# Avometer_v1_1_Simple.net
KiCad netlist of a schematic drawn in Altium Designer
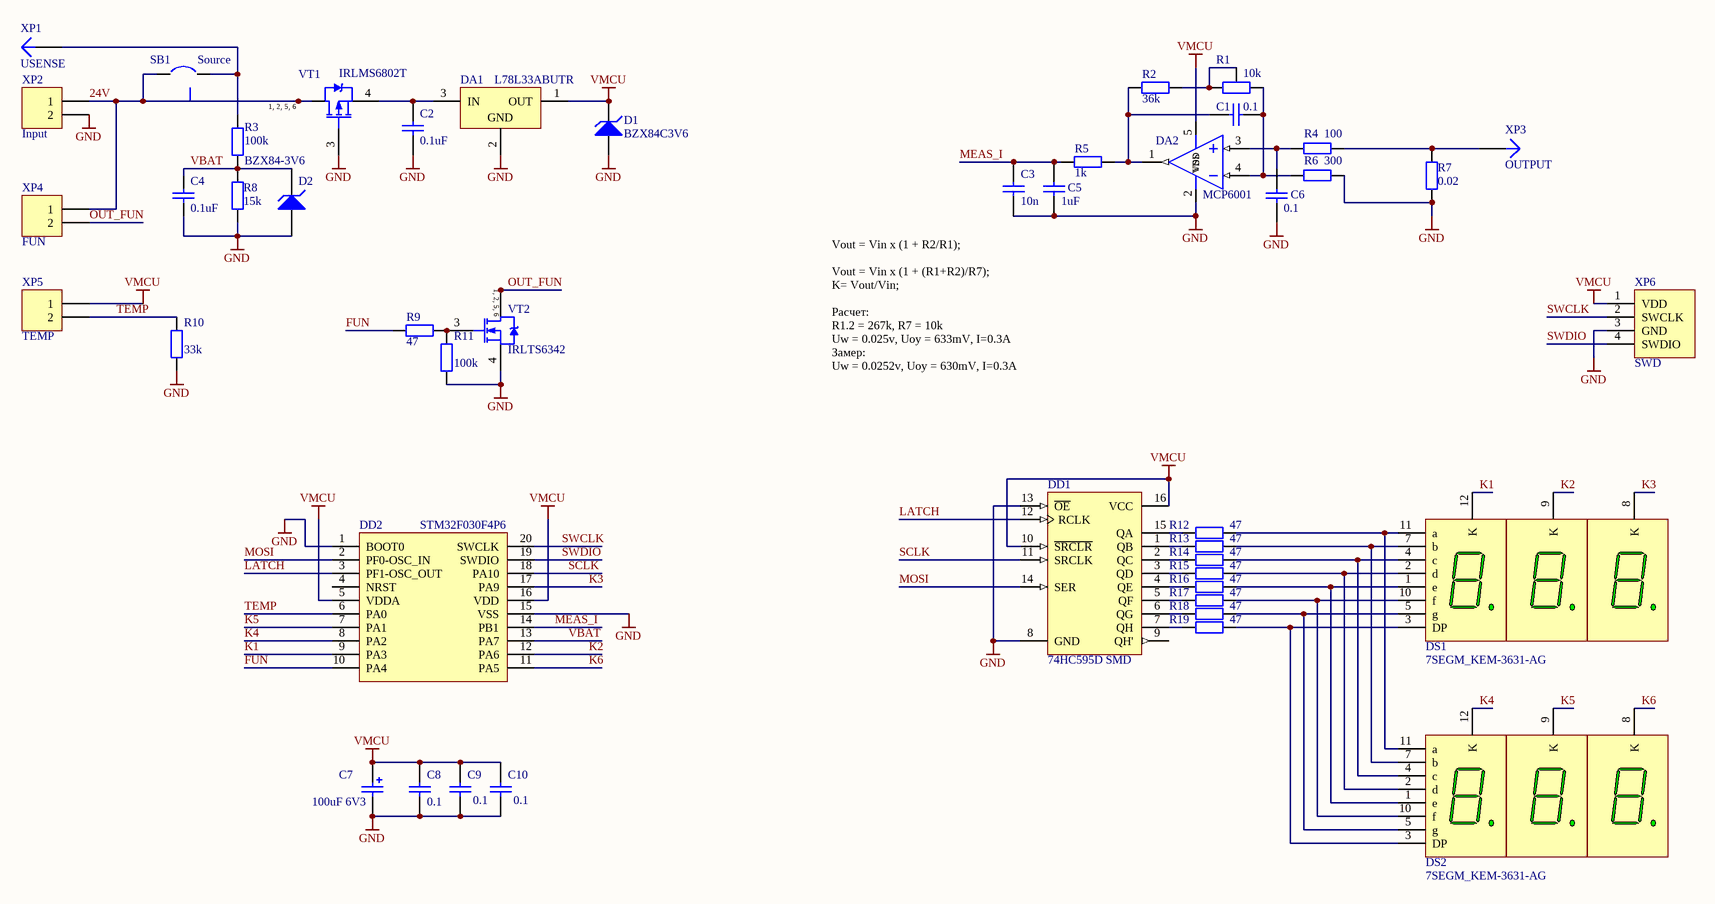
[diagram p0: Avometer v1.1 Simple.SchDoc]

(export (version "E")
  (design (tool "Eeschema 10.0.6"))
  (components
    (comp (ref "C1")
      (value "0.1")
      (footprint "CAP 0603_N")
      (description "Capacitor SMD")
      (libsource (lib "MyLibrary") (part "CAP_SMD"))
    )
    (comp (ref "C2")
      (value "0.1uF")
      (footprint "CAP 0603_N")
      (description "Capacitor SMD")
      (libsource (lib "MyLibrary") (part "CAP_SMD"))
    )
    (comp (ref "C3")
      (value "10n")
      (footprint "CAP 0603_N")
      (description "Capacitor SMD")
      (libsource (lib "MyLibrary") (part "CAP_SMD"))
    )
    (comp (ref "C4") (value "0.1uF") (footprint "CAP 0603_N") (libsource (lib "") (part "CAP_SMD_1")))
    (comp (ref "C5")
      (value "1uF")
      (footprint "CAP 0603_N")
      (description "Capacitor SMD")
      (libsource (lib "MyLibrary") (part "CAP_SMD"))
    )
    (comp (ref "C6")
      (value "0.1")
      (footprint "CAP 0603_N")
      (description "Capacitor SMD")
      (libsource (lib "MyLibrary") (part "CAP_SMD"))
    )
    (comp (ref "C7")
      (value "100uF 6V3")
      (footprint "CAP_TANT_B_TYPE_3528-21")
      (description "Capacitor SMD Tantalum")
      (libsource (lib "MyLibrary") (part "CAP_SMD_TANT"))
    )
    (comp (ref "C8")
      (value "0.1")
      (footprint "CAP 0603_N")
      (description "Capacitor SMD")
      (libsource (lib "MyLibrary") (part "CAP_SMD"))
    )
    (comp (ref "C9")
      (value "0.1")
      (footprint "CAP 0603_N")
      (description "Capacitor SMD")
      (libsource (lib "MyLibrary") (part "CAP_SMD"))
    )
    (comp (ref "C10")
      (value "0.1")
      (footprint "CAP 0603_N")
      (description "Capacitor SMD")
      (libsource (lib "MyLibrary") (part "CAP_SMD"))
    )
    (comp (ref "D1")
      (value "BZX84C3V6")
      (footprint "SOT-23_L")
      (description "Zener Diode")
      (fields (field (name "PUBLISHER") "Altium Limited"))
      (libsource (lib "") (part "BZX84_1"))
    )
    (comp (ref "D2")
      (value "BZX84-3V6")
      (footprint "SOT-23_L")
      (description "Zener Diode")
      (fields (field (name "PUBLISHER") "Altium Limited"))
      (libsource (lib "MyLibrary") (part "BZX84"))
    )
    (comp (ref "DA1")
      (value "L78L33ABUTR")
      (footprint "SOT-89")
      (description "Vin=30V Positive Voltage Regulator")
      (fields (field (name "PUBLISHER") "Altium Limited"))
      (libsource (lib "MyLibrary") (part "L78L33ABUTR"))
    )
    (comp (ref "DA2")
      (value "MCP6001")
      (footprint "SOT-23-5_L")
      (description "1 MHz, Low-Power Op Amp")
      (libsource (lib "MyLibrary") (part "MCP6001"))
    )
    (comp (ref "DD1")
      (value "74HC595D SMD")
      (footprint "SOIC-16_L")
      (description "8-Bit Shift Register with 3-State Output Registers")
      (fields (field (name "PUBLISHER") "Altium Limited"))
      (libsource (lib "MyLibrary") (part "74HC595D SMD"))
    )
    (comp (ref "DD2")
      (value "STM32F030F4P6")
      (footprint "TSSOP-20_N")
      (description "Cortex-M0 32-bit MCU, 16 KB Flash, 4 KB Internal RAM, 15 I/Os, 20-pin TSSOP, -40 to 85 degC")
      (libsource (lib "MyLibrary") (part "STM32F030F4P6"))
    )
    (comp (ref "DS1")
      (value "7SEGM_KEM-3631-AG")
      (footprint "7SEGM_KEM-3631-AG_BLUE")
      (description "7.62 mm Black Surface Green 7-Segment Display: CC, RH DP")
      (fields (field (name "PUBLISHER") "Altium Limited"))
      (libsource (lib "MyLibrary") (part "7SEGM_KEM-3631-AG"))
    )
    (comp (ref "DS2")
      (value "7SEGM_KEM-3631-AG")
      (footprint "7SEGM_KEM-3631-AG_RED")
      (description "7.62 mm Black Surface Green 7-Segment Display: CC, RH DP")
      (fields (field (name "PUBLISHER") "Altium Limited"))
      (libsource (lib "MyLibrary") (part "7SEGM_KEM-3631-AG"))
    )
    (comp (ref "R1")
      (value "10k")
      (footprint "RES VAR 1")
      (description "Tapped Resistor")
      (fields (field (name "PUBLISHER") "Altium Limited"))
      (libsource (lib "MyLibrary") (part "RES_SMD_Tap"))
    )
    (comp (ref "R2") (value "36k") (footprint "RES 0603_N") (libsource (lib "") (part "Resistor_SMD_1")))
    (comp (ref "R3") (value "100k") (footprint "RES 0603_N") (libsource (lib "MyLibrary") (part "RES_SMD")))
    (comp (ref "R4") (value "100") (footprint "RES 0603_N") (libsource (lib "") (part "Resistor_SMD_1")))
    (comp (ref "R5")
      (value "1k")
      (footprint "RES 0603_N")
      (description "Resistor")
      (libsource (lib "") (part "RES_SMD_1"))
    )
    (comp (ref "R6") (value "300") (footprint "RES 0603_N") (libsource (lib "") (part "Resistor_SMD_1")))
    (comp (ref "R7")
      (value "0.02")
      (footprint "RES 2512")
      (description "Resistor")
      (libsource (lib "MyLibrary") (part "RES_SMD"))
    )
    (comp (ref "R8") (value "15k") (footprint "RES 0603_N") (libsource (lib "MyLibrary") (part "RES_SMD")))
    (comp (ref "R9")
      (value "47")
      (footprint "RES 0603_N")
      (description "Chip Resistor")
      (libsource (lib "SyntecoLibrary") (part "RES_SMD"))
    )
    (comp (ref "R10")
      (value "33k")
      (footprint "RES 0603_N")
      (description "Chip Resistor")
      (libsource (lib "") (part "RES_SMD_1"))
    )
    (comp (ref "R11")
      (value "100k")
      (footprint "RES 0603_N")
      (description "Chip Resistor")
      (libsource (lib "") (part "RES_SMD_1"))
    )
    (comp (ref "R12")
      (value "47")
      (footprint "RES 0603_N")
      (libsource (lib "MyLibrary") (part "Resistor_SMD"))
    )
    (comp (ref "R13")
      (value "47")
      (footprint "RES 0603_N")
      (libsource (lib "MyLibrary") (part "Resistor_SMD"))
    )
    (comp (ref "R14")
      (value "47")
      (footprint "RES 0603_N")
      (libsource (lib "MyLibrary") (part "Resistor_SMD"))
    )
    (comp (ref "R15")
      (value "47")
      (footprint "RES 0603_N")
      (libsource (lib "MyLibrary") (part "Resistor_SMD"))
    )
    (comp (ref "R16")
      (value "47")
      (footprint "RES 0603_N")
      (libsource (lib "MyLibrary") (part "Resistor_SMD"))
    )
    (comp (ref "R17")
      (value "47")
      (footprint "RES 0603_N")
      (libsource (lib "MyLibrary") (part "Resistor_SMD"))
    )
    (comp (ref "R18")
      (value "47")
      (footprint "RES 0603_N")
      (libsource (lib "MyLibrary") (part "Resistor_SMD"))
    )
    (comp (ref "R19")
      (value "47")
      (footprint "RES 0603_N")
      (libsource (lib "MyLibrary") (part "Resistor_SMD"))
    )
    (comp (ref "SB1")
      (value "Source")
      (footprint "JUMPER_SOLDERED")
      (description "Jumper")
      (libsource (lib "MyLibrary") (part "Jumper_SMD"))
    )
    (comp (ref "VT1")
      (value "IRLMS6802T")
      (footprint "SOT-23-6_L")
      (description "P-Channel MOSFET 20V 4.5A")
      (fields (field (name "PUBLISHER") "Altium Limited"))
      (libsource (lib "MyLibrary") (part "IRLMS6802T"))
    )
    (comp (ref "VT2")
      (value "IRLTS6342")
      (footprint "TSOP-6")
      (description "30V, 6.7A, 1V N-Channel MOSFET")
      (fields (field (name "PUBLISHER") "Altium Limited"))
      (libsource (lib "MyLibrary") (part "IRLTS6342"))
    )
    (comp (ref "XP1")
      (value "USENSE")
      (footprint "CON_PIN")
      (description "Plug papa")
      (fields (field (name "PUBLISHER") "Altium Limited"))
      (libsource (lib "MyLibrary") (part "CON_1x1_PIN"))
    )
    (comp (ref "XP2")
      (value "Input")
      (footprint "CON_5.08MM_1X2")
      (description "Header, 2-Pin")
      (fields (field (name "PUBLISHER") "Altium Limited"))
      (libsource (lib "MyLibrary") (part "CON_5.08mm_1x2"))
    )
    (comp (ref "XP3")
      (value "OUTPUT")
      (footprint "CON_PIN")
      (description "Plug papa")
      (fields (field (name "PUBLISHER") "Altium Limited"))
      (libsource (lib "MyLibrary") (part "CON_1x1_PIN"))
    )
    (comp (ref "XP4")
      (value "FUN")
      (footprint "CON_2.54MM_1X2")
      (description "Header, 2-Pin")
      (fields (field (name "PUBLISHER") "Altium Limited"))
      (libsource (lib "MyLibrary") (part "CON_2.54mm_1x2"))
    )
    (comp (ref "XP5")
      (value "TEMP")
      (footprint "CON_2.54MM_1X2")
      (description "Header, 2-Pin")
      (fields (field (name "PUBLISHER") "Altium Limited"))
      (libsource (lib "MyLibrary") (part "CON_2.54mm_1x2"))
    )
    (comp (ref "XP6")
      (value "SWD")
      (footprint "CON_1.27MM_1X4_SWD")
      (description "Header, 3-Pin")
      (fields (field (name "PUBLISHER") "Altium Limited"))
      (libsource (lib "MyLibrary") (part "CON_1.27mm_1x4_SWD"))
    )
  )
  (nets
    (net (code "1") (name "/24V") (class "Default")
      (node (ref "SB1") (pin "1") (pinfunction "1_1") (pintype "passive"))
      (node (ref "VT1") (pin "1") (pinfunction "D_1") (pintype "passive"))
      (node (ref "VT1") (pin "2") (pinfunction "D_2") (pintype "passive"))
      (node (ref "VT1") (pin "5") (pinfunction "D_5") (pintype "passive"))
      (node (ref "VT1") (pin "6") (pinfunction "D_6") (pintype "passive"))
      (node (ref "XP2") (pin "1") (pinfunction "1_1") (pintype "passive"))
      (node (ref "XP4") (pin "1") (pinfunction "1_1") (pintype "passive"))
    )
    (net (code "2") (name "/FUN") (class "Default")
      (node (ref "DD2") (pin "10") (pinfunction "PA4_10") (pintype "passive"))
      (node (ref "R9") (pin "2") (pinfunction "2_2") (pintype "passive"))
    )
    (net (code "3") (name "/K1") (class "Default")
      (node (ref "DD2") (pin "9") (pinfunction "PA3_9") (pintype "passive"))
      (node (ref "DS1") (pin "12") (pinfunction "K_12") (pintype "passive"))
    )
    (net (code "4") (name "/K2") (class "Default")
      (node (ref "DD2") (pin "12") (pinfunction "PA6_12") (pintype "passive"))
      (node (ref "DS1") (pin "9") (pinfunction "K_9") (pintype "passive"))
    )
    (net (code "5") (name "/K3") (class "Default")
      (node (ref "DD2") (pin "17") (pinfunction "PA9_17") (pintype "passive"))
      (node (ref "DS1") (pin "8") (pinfunction "K_8") (pintype "passive"))
    )
    (net (code "6") (name "/K4") (class "Default")
      (node (ref "DD2") (pin "8") (pinfunction "PA2_8") (pintype "passive"))
      (node (ref "DS2") (pin "12") (pinfunction "K_12") (pintype "passive"))
    )
    (net (code "7") (name "/K5") (class "Default")
      (node (ref "DD2") (pin "7") (pinfunction "PA1_7") (pintype "passive"))
      (node (ref "DS2") (pin "9") (pinfunction "K_9") (pintype "passive"))
    )
    (net (code "8") (name "/K6") (class "Default")
      (node (ref "DD2") (pin "11") (pinfunction "PA5_11") (pintype "passive"))
      (node (ref "DS2") (pin "8") (pinfunction "K_8") (pintype "passive"))
    )
    (net (code "9") (name "/LATCH") (class "Default")
      (node (ref "DD1") (pin "12") (pinfunction "RCLK_12") (pintype "input"))
      (node (ref "DD2") (pin "3") (pinfunction "PF1-OSC_OUT_3") (pintype "passive"))
    )
    (net (code "10") (name "/MEAS_I") (class "Default")
      (node (ref "C3") (pin "2") (pinfunction "2_2") (pintype "passive"))
      (node (ref "C5") (pin "2") (pinfunction "2_2") (pintype "passive"))
      (node (ref "DD2") (pin "14") (pinfunction "PB1_14") (pintype "passive"))
      (node (ref "R5") (pin "1") (pinfunction "1_1") (pintype "passive"))
    )
    (net (code "11") (name "/MOSI") (class "Default")
      (node (ref "DD1") (pin "14") (pinfunction "SER_14") (pintype "input"))
      (node (ref "DD2") (pin "2") (pinfunction "PF0-OSC_IN_2") (pintype "passive"))
    )
    (net (code "12") (name "/OUT_FUN") (class "Default")
      (node (ref "VT2") (pin "1") (pinfunction "D_1") (pintype "passive"))
      (node (ref "VT2") (pin "2") (pinfunction "D_2") (pintype "passive"))
      (node (ref "VT2") (pin "5") (pinfunction "D_5") (pintype "passive"))
      (node (ref "VT2") (pin "6") (pinfunction "D_6") (pintype "passive"))
      (node (ref "XP4") (pin "2") (pinfunction "2_2") (pintype "passive"))
    )
    (net (code "13") (name "/SCLK") (class "Default")
      (node (ref "DD1") (pin "11") (pinfunction "SRCLK_11") (pintype "input"))
      (node (ref "DD2") (pin "18") (pinfunction "PA10_18") (pintype "passive"))
    )
    (net (code "14") (name "/SWCLK") (class "Default")
      (node (ref "DD2") (pin "20") (pinfunction "SWCLK_20") (pintype "passive"))
      (node (ref "XP6") (pin "2") (pinfunction "SWCLK_2") (pintype "passive"))
    )
    (net (code "15") (name "/SWDIO") (class "Default")
      (node (ref "DD2") (pin "19") (pinfunction "SWDIO_19") (pintype "passive"))
      (node (ref "XP6") (pin "4") (pinfunction "SWDIO_4") (pintype "passive"))
    )
    (net (code "16") (name "/TEMP") (class "Default")
      (node (ref "DD2") (pin "6") (pinfunction "PA0_6") (pintype "passive"))
      (node (ref "R10") (pin "2") (pinfunction "2_2") (pintype "passive"))
      (node (ref "XP5") (pin "2") (pinfunction "2_2") (pintype "passive"))
    )
    (net (code "17") (name "/VBAT") (class "Default")
      (node (ref "C4") (pin "2") (pinfunction "2_2") (pintype "passive"))
      (node (ref "D2") (pin "3") (pinfunction "K_3") (pintype "passive"))
      (node (ref "DD2") (pin "13") (pinfunction "PA7_13") (pintype "passive"))
      (node (ref "R3") (pin "1") (pinfunction "1_1") (pintype "passive"))
      (node (ref "R8") (pin "2") (pinfunction "2_2") (pintype "passive"))
    )
    (net (code "18") (name "GND") (class "Default")
      (node (ref "C10") (pin "2") (pinfunction "2_2") (pintype "passive"))
      (node (ref "C2") (pin "1") (pinfunction "1_1") (pintype "passive"))
      (node (ref "C3") (pin "1") (pinfunction "1_1") (pintype "passive"))
      (node (ref "C4") (pin "1") (pinfunction "1_1") (pintype "passive"))
      (node (ref "C5") (pin "1") (pinfunction "1_1") (pintype "passive"))
      (node (ref "C6") (pin "2") (pinfunction "2_2") (pintype "passive"))
      (node (ref "C7") (pin "2") (pinfunction "2_2") (pintype "passive"))
      (node (ref "C8") (pin "1") (pinfunction "1_1") (pintype "passive"))
      (node (ref "C9") (pin "2") (pinfunction "2_2") (pintype "passive"))
      (node (ref "D1") (pin "1") (pinfunction "A_1") (pintype "passive"))
      (node (ref "D2") (pin "1") (pinfunction "A_1") (pintype "passive"))
      (node (ref "DA1") (pin "2") (pinfunction "GND_2") (pintype "power_in"))
      (node (ref "DA2") (pin "2") (pinfunction "VSS_2") (pintype "power_in"))
      (node (ref "DD1") (pin "13") (pinfunction "~{OE}_13") (pintype "input"))
      (node (ref "DD1") (pin "8") (pinfunction "GND_8") (pintype "power_in"))
      (node (ref "DD2") (pin "1") (pinfunction "BOOT0_1") (pintype "passive"))
      (node (ref "DD2") (pin "15") (pinfunction "VSS_15") (pintype "passive"))
      (node (ref "R10") (pin "1") (pinfunction "1_1") (pintype "passive"))
      (node (ref "R11") (pin "1") (pinfunction "1_1") (pintype "passive"))
      (node (ref "R6") (pin "1") (pinfunction "1_1") (pintype "passive"))
      (node (ref "R7") (pin "1") (pinfunction "1_1") (pintype "passive"))
      (node (ref "R8") (pin "1") (pinfunction "1_1") (pintype "passive"))
      (node (ref "VT1") (pin "3") (pinfunction "G_3") (pintype "passive"))
      (node (ref "VT2") (pin "4") (pinfunction "S_4") (pintype "passive"))
      (node (ref "XP2") (pin "2") (pinfunction "2_2") (pintype "passive"))
      (node (ref "XP6") (pin "3") (pinfunction "GND_3") (pintype "passive"))
    )
    (net (code "19") (name "Net-(DA1-IN)") (class "Default")
      (node (ref "C2") (pin "2") (pinfunction "2_2") (pintype "passive"))
      (node (ref "DA1") (pin "3") (pinfunction "IN_3") (pintype "power_in"))
      (node (ref "VT1") (pin "4") (pinfunction "S_4") (pintype "passive"))
    )
    (net (code "20") (name "Net-(DA2-VIN+)") (class "Default")
      (node (ref "C6") (pin "1") (pinfunction "1_1") (pintype "passive"))
      (node (ref "DA2") (pin "3") (pinfunction "VIN+_3") (pintype "input"))
      (node (ref "R4") (pin "2") (pinfunction "2_2") (pintype "passive"))
    )
    (net (code "21") (name "Net-(DA2-VIN-)") (class "Default")
      (node (ref "C1") (pin "2") (pinfunction "2_2") (pintype "passive"))
      (node (ref "DA2") (pin "4") (pinfunction "VIN-_4") (pintype "input"))
      (node (ref "R1") (pin "3") (pinfunction "B_3") (pintype "passive"))
      (node (ref "R6") (pin "2") (pinfunction "2_2") (pintype "passive"))
    )
    (net (code "22") (name "Net-(DA2-VOUT)") (class "Default")
      (node (ref "C1") (pin "1") (pinfunction "1_1") (pintype "passive"))
      (node (ref "DA2") (pin "1") (pinfunction "VOUT_1") (pintype "output"))
      (node (ref "R2") (pin "2") (pinfunction "2_2") (pintype "passive"))
      (node (ref "R5") (pin "2") (pinfunction "2_2") (pintype "passive"))
    )
    (net (code "23") (name "Net-(DD1-QA)") (class "Default")
      (node (ref "DD1") (pin "15") (pinfunction "QA_15") (pintype "tri_state"))
      (node (ref "R12") (pin "1") (pinfunction "1_1") (pintype "passive"))
    )
    (net (code "24") (name "Net-(DD1-QB)") (class "Default")
      (node (ref "DD1") (pin "1") (pinfunction "QB_1") (pintype "tri_state"))
      (node (ref "R13") (pin "1") (pinfunction "1_1") (pintype "passive"))
    )
    (net (code "25") (name "Net-(DD1-QC)") (class "Default")
      (node (ref "DD1") (pin "2") (pinfunction "QC_2") (pintype "tri_state"))
      (node (ref "R14") (pin "1") (pinfunction "1_1") (pintype "passive"))
    )
    (net (code "26") (name "Net-(DD1-QD)") (class "Default")
      (node (ref "DD1") (pin "3") (pinfunction "QD_3") (pintype "tri_state"))
      (node (ref "R15") (pin "1") (pinfunction "1_1") (pintype "passive"))
    )
    (net (code "27") (name "Net-(DD1-QE)") (class "Default")
      (node (ref "DD1") (pin "4") (pinfunction "QE_4") (pintype "tri_state"))
      (node (ref "R16") (pin "1") (pinfunction "1_1") (pintype "passive"))
    )
    (net (code "28") (name "Net-(DD1-QF)") (class "Default")
      (node (ref "DD1") (pin "5") (pinfunction "QF_5") (pintype "tri_state"))
      (node (ref "R17") (pin "1") (pinfunction "1_1") (pintype "passive"))
    )
    (net (code "29") (name "Net-(DD1-QG)") (class "Default")
      (node (ref "DD1") (pin "6") (pinfunction "QG_6") (pintype "tri_state"))
      (node (ref "R18") (pin "1") (pinfunction "1_1") (pintype "passive"))
    )
    (net (code "30") (name "Net-(DD1-QH)") (class "Default")
      (node (ref "DD1") (pin "7") (pinfunction "QH_7") (pintype "tri_state"))
      (node (ref "R19") (pin "1") (pinfunction "1_1") (pintype "passive"))
    )
    (net (code "31") (name "Net-(DS1-DP)") (class "Default")
      (node (ref "DS1") (pin "3") (pinfunction "DP_3") (pintype "passive"))
      (node (ref "DS2") (pin "3") (pinfunction "DP_3") (pintype "passive"))
      (node (ref "R19") (pin "2") (pinfunction "2_2") (pintype "passive"))
    )
    (net (code "32") (name "Net-(DS1-a)") (class "Default")
      (node (ref "DS1") (pin "11") (pinfunction "a_11") (pintype "passive"))
      (node (ref "DS2") (pin "11") (pinfunction "a_11") (pintype "passive"))
      (node (ref "R12") (pin "2") (pinfunction "2_2") (pintype "passive"))
    )
    (net (code "33") (name "Net-(DS1-b)") (class "Default")
      (node (ref "DS1") (pin "7") (pinfunction "b_7") (pintype "passive"))
      (node (ref "DS2") (pin "7") (pinfunction "b_7") (pintype "passive"))
      (node (ref "R13") (pin "2") (pinfunction "2_2") (pintype "passive"))
    )
    (net (code "34") (name "Net-(DS1-c)") (class "Default")
      (node (ref "DS1") (pin "4") (pinfunction "c_4") (pintype "passive"))
      (node (ref "DS2") (pin "4") (pinfunction "c_4") (pintype "passive"))
      (node (ref "R14") (pin "2") (pinfunction "2_2") (pintype "passive"))
    )
    (net (code "35") (name "Net-(DS1-d)") (class "Default")
      (node (ref "DS1") (pin "2") (pinfunction "d_2") (pintype "passive"))
      (node (ref "DS2") (pin "2") (pinfunction "d_2") (pintype "passive"))
      (node (ref "R15") (pin "2") (pinfunction "2_2") (pintype "passive"))
    )
    (net (code "36") (name "Net-(DS1-e)") (class "Default")
      (node (ref "DS1") (pin "1") (pinfunction "e_1") (pintype "passive"))
      (node (ref "DS2") (pin "1") (pinfunction "e_1") (pintype "passive"))
      (node (ref "R16") (pin "2") (pinfunction "2_2") (pintype "passive"))
    )
    (net (code "37") (name "Net-(DS1-f)") (class "Default")
      (node (ref "DS1") (pin "10") (pinfunction "f_10") (pintype "passive"))
      (node (ref "DS2") (pin "10") (pinfunction "f_10") (pintype "passive"))
      (node (ref "R17") (pin "2") (pinfunction "2_2") (pintype "passive"))
    )
    (net (code "38") (name "Net-(DS1-g)") (class "Default")
      (node (ref "DS1") (pin "5") (pinfunction "g_5") (pintype "passive"))
      (node (ref "DS2") (pin "5") (pinfunction "g_5") (pintype "passive"))
      (node (ref "R18") (pin "2") (pinfunction "2_2") (pintype "passive"))
    )
    (net (code "39") (name "Net-(R1-A)") (class "Default")
      (node (ref "R1") (pin "1") (pinfunction "A_1") (pintype "passive"))
      (node (ref "R1") (pin "2") (pinfunction "TAP_2") (pintype "passive"))
      (node (ref "R2") (pin "1") (pinfunction "1_1") (pintype "passive"))
    )
    (net (code "40") (name "Net-(R3-Pad2)") (class "Default")
      (node (ref "R3") (pin "2") (pinfunction "2_2") (pintype "passive"))
      (node (ref "SB1") (pin "2") (pinfunction "2_2") (pintype "passive"))
      (node (ref "XP1") (pin "1") (pinfunction "1_1") (pintype "passive"))
    )
    (net (code "41") (name "Net-(R4-Pad1)") (class "Default")
      (node (ref "R4") (pin "1") (pinfunction "1_1") (pintype "passive"))
      (node (ref "R7") (pin "2") (pinfunction "2_2") (pintype "passive"))
      (node (ref "XP3") (pin "1") (pinfunction "1_1") (pintype "passive"))
    )
    (net (code "42") (name "Net-(VT2-G)") (class "Default")
      (node (ref "R11") (pin "2") (pinfunction "2_2") (pintype "passive"))
      (node (ref "R9") (pin "1") (pinfunction "1_1") (pintype "passive"))
      (node (ref "VT2") (pin "3") (pinfunction "G_3") (pintype "passive"))
    )
    (net (code "43") (name "VMCU") (class "Default")
      (node (ref "C10") (pin "1") (pinfunction "1_1") (pintype "passive"))
      (node (ref "C7") (pin "1") (pinfunction "1_1") (pintype "passive"))
      (node (ref "C8") (pin "2") (pinfunction "2_2") (pintype "passive"))
      (node (ref "C9") (pin "1") (pinfunction "1_1") (pintype "passive"))
      (node (ref "D1") (pin "3") (pinfunction "K_3") (pintype "passive"))
      (node (ref "DA1") (pin "1") (pinfunction "OUT_1") (pintype "power_in"))
      (node (ref "DA2") (pin "5") (pinfunction "VDD_5") (pintype "power_in"))
      (node (ref "DD1") (pin "10") (pinfunction "~{SRCLR}_10") (pintype "input"))
      (node (ref "DD1") (pin "16") (pinfunction "VCC_16") (pintype "power_in"))
      (node (ref "DD2") (pin "16") (pinfunction "VDD_16") (pintype "passive"))
      (node (ref "DD2") (pin "5") (pinfunction "VDDA_5") (pintype "passive"))
      (node (ref "XP5") (pin "1") (pinfunction "1_1") (pintype "passive"))
      (node (ref "XP6") (pin "1") (pinfunction "VDD_1") (pintype "passive"))
    )
    (net (code "44") (name "unconnected-(DD1-QH'-Pad9)") (class "Default")
      (node (ref "DD1") (pin "9") (pinfunction "QH'_9") (pintype "output"))
    )
    (net (code "45") (name "unconnected-(DD2-NRST-Pad4)") (class "Default")
      (node (ref "DD2") (pin "4") (pinfunction "NRST_4") (pintype "passive"))
    )
  )
)
